# EPS_Battery_Controller_RLCL.net
KiCad netlist of a schematic drawn in Altium Designer
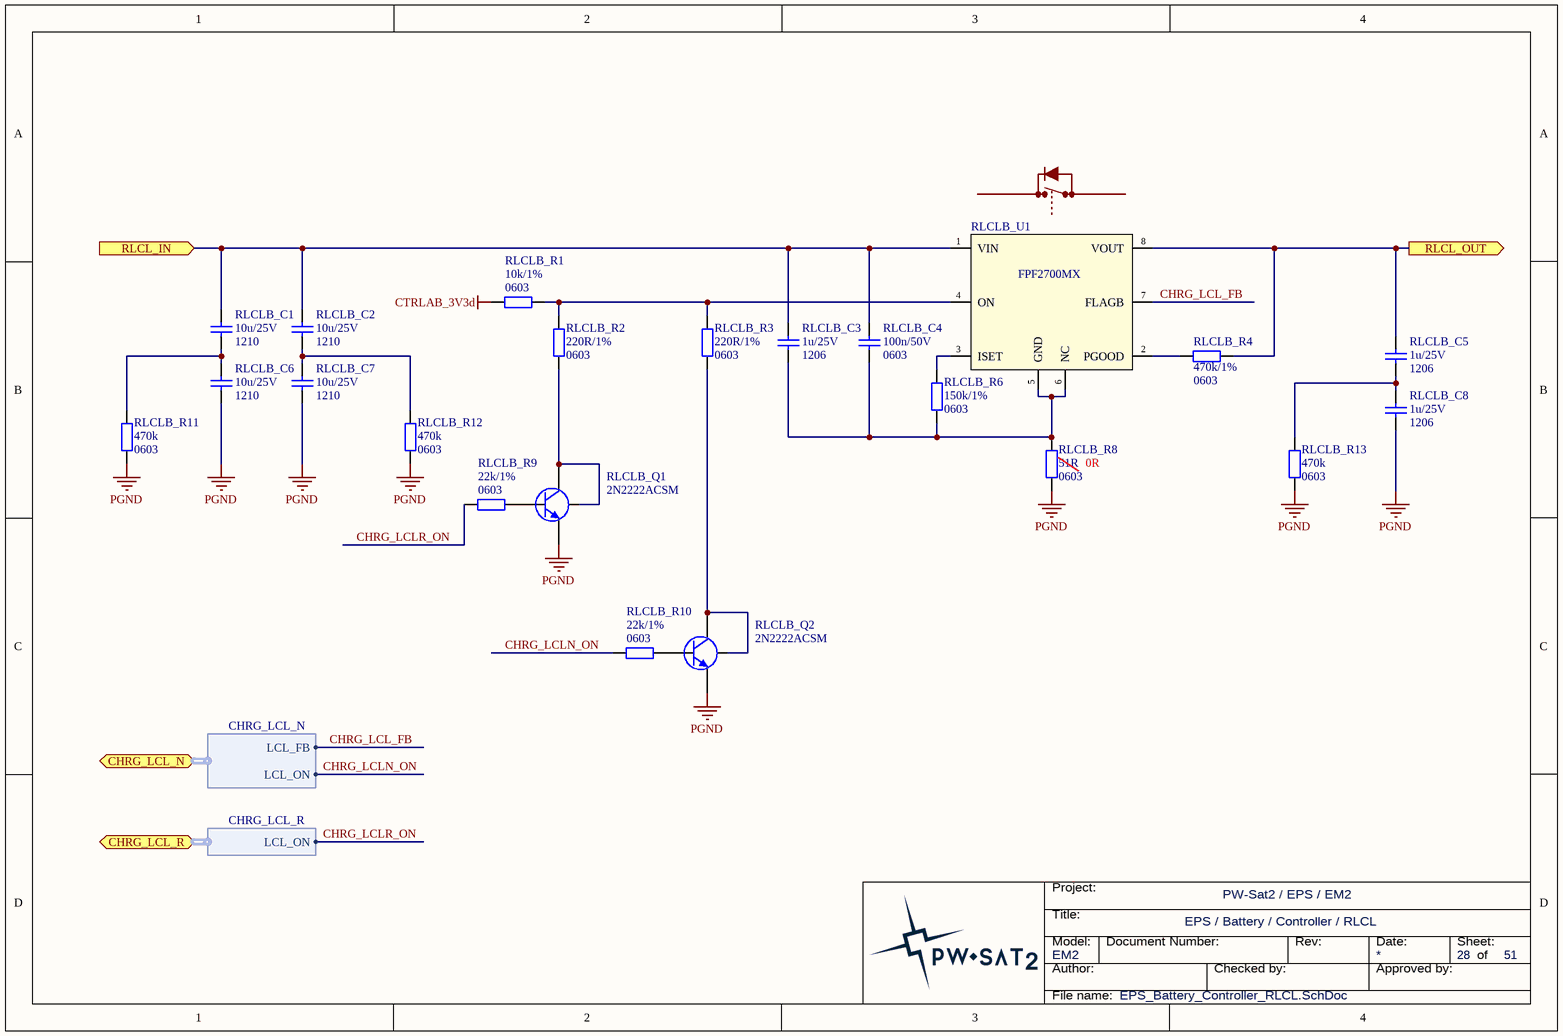
[diagram p0: EPS_Battery_Controller_RLCL.SchDoc]

(export (version "E")
  (design (tool "Eeschema 10.0.6"))
  (components
    (comp (ref "RLCLB_C1")
      (value "10u/25V")
      (footprint "SMD_Capacitor_1210")
      (description "Ceramic Cap Murata Automotive 10u/25V X7R 1210")
      (fields
        (field (name "MANUFACTURER") "Murata")
        (field (name "MANUFACTURERPARTNUMBER") "GCJ32ER71E106KA12L")
        (field (name "PACKAGE") "1210")
      )
      (libsource (lib "capacitors") (part "Cer_GCJ32ER71E106KA12L"))
    )
    (comp (ref "RLCLB_C2")
      (value "10u/25V")
      (footprint "SMD_Capacitor_1210")
      (description "Ceramic Cap Murata Automotive 10u/25V X7R 1210")
      (fields
        (field (name "MANUFACTURER") "Murata")
        (field (name "MANUFACTURERPARTNUMBER") "GCJ32ER71E106KA12L")
        (field (name "PACKAGE") "1210")
      )
      (libsource (lib "capacitors") (part "Cer_GCJ32ER71E106KA12L"))
    )
    (comp (ref "RLCLB_C3")
      (value "1u/25V")
      (footprint "SMD_Capacitor_1206")
      (description "Ceramic Cap Kemet COTS 1u/25V X7R 1206")
      (fields
        (field (name "MANUFACTURERPARTNUMBER") "C1206T105K3RALTU")
        (field (name "MANUFACTURER") "Kemet")
        (field (name "PACKAGE") "1206")
      )
      (libsource (lib "capacitors") (part "Cer_C1206T105K3RALTU"))
    )
    (comp (ref "RLCLB_C4")
      (value "100n/50V")
      (footprint "SMD_Capacitor_0603")
      (description "Ceramic Cap Murata Automotive 100n/50V X7R 0603")
      (fields
        (field (name "MANUFACTURER") "Murata")
        (field (name "MANUFACTURERPARTNUMBER") "GCJ188R71H104KA12D")
        (field (name "PACKAGE") "0603")
      )
      (libsource (lib "capacitors") (part "Cer_GCJ188R71H104KA12D"))
    )
    (comp (ref "RLCLB_C5")
      (value "1u/25V")
      (footprint "SMD_Capacitor_1206")
      (description "Ceramic Cap Kemet COTS 1u/25V X7R 1206")
      (fields
        (field (name "MANUFACTURERPARTNUMBER") "C1206T105K3RALTU")
        (field (name "MANUFACTURER") "Kemet")
        (field (name "PACKAGE") "1206")
      )
      (libsource (lib "capacitors") (part "Cer_C1206T105K3RALTU"))
    )
    (comp (ref "RLCLB_C6")
      (value "10u/25V")
      (footprint "SMD_Capacitor_1210")
      (description "Ceramic Cap Murata Automotive 10u/25V X7R 1210")
      (fields
        (field (name "MANUFACTURER") "Murata")
        (field (name "MANUFACTURERPARTNUMBER") "GCJ32ER71E106KA12L")
        (field (name "PACKAGE") "1210")
      )
      (libsource (lib "capacitors") (part "Cer_GCJ32ER71E106KA12L"))
    )
    (comp (ref "RLCLB_C7")
      (value "10u/25V")
      (footprint "SMD_Capacitor_1210")
      (description "Ceramic Cap Murata Automotive 10u/25V X7R 1210")
      (fields
        (field (name "MANUFACTURER") "Murata")
        (field (name "MANUFACTURERPARTNUMBER") "GCJ32ER71E106KA12L")
        (field (name "PACKAGE") "1210")
      )
      (libsource (lib "capacitors") (part "Cer_GCJ32ER71E106KA12L"))
    )
    (comp (ref "RLCLB_C8")
      (value "1u/25V")
      (footprint "SMD_Capacitor_1206")
      (description "Ceramic Cap Kemet COTS 1u/25V X7R 1206")
      (fields
        (field (name "MANUFACTURERPARTNUMBER") "C1206T105K3RALTU")
        (field (name "MANUFACTURER") "Kemet")
        (field (name "PACKAGE") "1206")
      )
      (libsource (lib "capacitors") (part "Cer_C1206T105K3RALTU"))
    )
    (comp (ref "RLCLB_Q1")
      (value "2N2222ACSM")
      (footprint "LCC1-4_BEC")
      (description "Silicon Planar Epitaxial NPN Transistor.")
      (fields (field (name "MANUFACTURER") "Semelab-TT"))
      (libsource (lib "transistors") (part "2N2222ACSM"))
    )
    (comp (ref "RLCLB_Q2")
      (value "2N2222ACSM")
      (footprint "LCC1-4_BEC")
      (description "Silicon Planar Epitaxial NPN Transistor.")
      (fields (field (name "MANUFACTURER") "Semelab-TT"))
      (libsource (lib "transistors") (part "2N2222ACSM"))
    )
    (comp (ref "RLCLB_R1")
      (value "10k/1%")
      (footprint "SMD_Resistor_0603")
      (fields (field (name "PACKAGE") "0603"))
      (libsource (lib "resistors") (part "Res"))
    )
    (comp (ref "RLCLB_R2")
      (value "220R/1%")
      (footprint "SMD_Resistor_0603")
      (fields (field (name "PACKAGE") "0603"))
      (libsource (lib "resistors") (part "Res"))
    )
    (comp (ref "RLCLB_R3")
      (value "220R/1%")
      (footprint "SMD_Resistor_0603")
      (fields (field (name "PACKAGE") "0603"))
      (libsource (lib "resistors") (part "Res"))
    )
    (comp (ref "RLCLB_R4")
      (value "470k/1%")
      (footprint "SMD_Resistor_0603")
      (fields (field (name "PACKAGE") "0603"))
      (libsource (lib "") (part "Res_2"))
    )
    (comp (ref "RLCLB_R6")
      (value "150k/1%")
      (footprint "SMD_Resistor_0603")
      (fields (field (name "PACKAGE") "0603"))
      (libsource (lib "resistors") (part "Res"))
    )
    (comp (ref "RLCLB_R8")
      (value "51R")
      (footprint "SMD_Resistor_0603")
      (fields (field (name "PACKAGE") "0603"))
      (libsource (lib "resistors") (part "Res"))
    )
    (comp (ref "RLCLB_R9")
      (value "22k/1%")
      (footprint "SMD_Resistor_0603")
      (fields (field (name "PACKAGE") "0603"))
      (libsource (lib "") (part "Res_1"))
    )
    (comp (ref "RLCLB_R10")
      (value "22k/1%")
      (footprint "SMD_Resistor_0603")
      (fields (field (name "PACKAGE") "0603"))
      (libsource (lib "") (part "Res_1"))
    )
    (comp (ref "RLCLB_R11")
      (value "470k")
      (footprint "SMD_Resistor_0603")
      (fields (field (name "PACKAGE") "0603"))
      (libsource (lib "resistors") (part "Res"))
    )
    (comp (ref "RLCLB_R12")
      (value "470k")
      (footprint "SMD_Resistor_0603")
      (fields (field (name "PACKAGE") "0603"))
      (libsource (lib "resistors") (part "Res"))
    )
    (comp (ref "RLCLB_R13")
      (value "470k")
      (footprint "SMD_Resistor_0603")
      (fields (field (name "PACKAGE") "0603"))
      (libsource (lib "resistors") (part "Res"))
    )
    (comp (ref "RLCLB_U1")
      (value "FPF2700MX")
      (footprint "SOIC-8-N")
      (description "Adj over-current protection 0.4-2A, Load Switch")
      (fields (field (name "MANUFACTURER") "Fairchild Semiconductor"))
      (libsource (lib "microcircuits") (part "FPF2700MX"))
    )
  )
  (nets
    (net (code "3") (name "/CHRG_LCLN_ON") (class "Default")
      (node (ref "RLCLB_R10") (pin "1") (pinfunction "1_1") (pintype "passive"))
    )
    (net (code "4") (name "/CHRG_LCLR_ON") (class "Default")
      (node (ref "RLCLB_R9") (pin "1") (pinfunction "1_1") (pintype "passive"))
    )
    (net (code "5") (name "/CHRG_LCL_FB") (class "Default")
      (node (ref "RLCLB_U1") (pin "7") (pinfunction "FLAGB_7") (pintype "passive"))
    )
    (net (code "6") (name "/RLCL_IN") (class "Default")
      (node (ref "RLCLB_C1") (pin "1") (pinfunction "1_1") (pintype "passive"))
      (node (ref "RLCLB_C2") (pin "1") (pinfunction "1_1") (pintype "passive"))
      (node (ref "RLCLB_C3") (pin "1") (pinfunction "1_1") (pintype "passive"))
      (node (ref "RLCLB_C4") (pin "1") (pinfunction "1_1") (pintype "passive"))
      (node (ref "RLCLB_U1") (pin "1") (pinfunction "VIN_1") (pintype "passive"))
    )
    (net (code "7") (name "/RLCL_OUT") (class "Default")
      (node (ref "RLCLB_C5") (pin "1") (pinfunction "1_1") (pintype "passive"))
      (node (ref "RLCLB_R4") (pin "2") (pinfunction "2_2") (pintype "passive"))
      (node (ref "RLCLB_U1") (pin "8") (pinfunction "VOUT_8") (pintype "passive"))
    )
    (net (code "10") (name "CTRLAB_3V3d") (class "Default")
      (node (ref "RLCLB_R1") (pin "2") (pinfunction "2_2") (pintype "passive"))
    )
    (net (code "11") (name "Net-(RLCLB_C1-Pad2)") (class "Default")
      (node (ref "RLCLB_C1") (pin "2") (pinfunction "2_2") (pintype "passive"))
      (node (ref "RLCLB_C6") (pin "1") (pinfunction "1_1") (pintype "passive"))
      (node (ref "RLCLB_R11") (pin "1") (pinfunction "1_1") (pintype "passive"))
    )
    (net (code "12") (name "Net-(RLCLB_C2-Pad2)") (class "Default")
      (node (ref "RLCLB_C2") (pin "2") (pinfunction "2_2") (pintype "passive"))
      (node (ref "RLCLB_C7") (pin "1") (pinfunction "1_1") (pintype "passive"))
      (node (ref "RLCLB_R12") (pin "1") (pinfunction "1_1") (pintype "passive"))
    )
    (net (code "13") (name "Net-(RLCLB_C5-Pad2)") (class "Default")
      (node (ref "RLCLB_C5") (pin "2") (pinfunction "2_2") (pintype "passive"))
      (node (ref "RLCLB_C8") (pin "1") (pinfunction "1_1") (pintype "passive"))
      (node (ref "RLCLB_R13") (pin "1") (pinfunction "1_1") (pintype "passive"))
    )
    (net (code "14") (name "Net-(RLCLB_Q1-PadB)") (class "Default")
      (node (ref "RLCLB_Q1") (pin "B") (pinfunction "B_B") (pintype "passive"))
      (node (ref "RLCLB_R9") (pin "2") (pinfunction "2_2") (pintype "passive"))
    )
    (net (code "15") (name "Net-(RLCLB_Q1-PadC)") (class "Default")
      (node (ref "RLCLB_Q1") (pin "C") (pinfunction "C_C") (pintype "passive"))
      (node (ref "RLCLB_Q1") (pin "Shield") (pinfunction "Shield_Shield") (pintype "passive"))
      (node (ref "RLCLB_R2") (pin "2") (pinfunction "2_2") (pintype "passive"))
    )
    (net (code "16") (name "Net-(RLCLB_Q2-PadB)") (class "Default")
      (node (ref "RLCLB_Q2") (pin "B") (pinfunction "B_B") (pintype "passive"))
      (node (ref "RLCLB_R10") (pin "2") (pinfunction "2_2") (pintype "passive"))
    )
    (net (code "17") (name "Net-(RLCLB_Q2-PadC)") (class "Default")
      (node (ref "RLCLB_Q2") (pin "C") (pinfunction "C_C") (pintype "passive"))
      (node (ref "RLCLB_Q2") (pin "Shield") (pinfunction "Shield_Shield") (pintype "passive"))
      (node (ref "RLCLB_R3") (pin "2") (pinfunction "2_2") (pintype "passive"))
    )
    (net (code "18") (name "Net-(RLCLB_U1-GND)") (class "Default")
      (node (ref "RLCLB_C3") (pin "2") (pinfunction "2_2") (pintype "passive"))
      (node (ref "RLCLB_C4") (pin "2") (pinfunction "2_2") (pintype "passive"))
      (node (ref "RLCLB_R6") (pin "2") (pinfunction "2_2") (pintype "passive"))
      (node (ref "RLCLB_R8") (pin "1") (pinfunction "1_1") (pintype "passive"))
      (node (ref "RLCLB_U1") (pin "5") (pinfunction "GND_5") (pintype "passive"))
      (node (ref "RLCLB_U1") (pin "6") (pinfunction "NC_6") (pintype "passive"))
    )
    (net (code "19") (name "Net-(RLCLB_U1-ISET)") (class "Default")
      (node (ref "RLCLB_R6") (pin "1") (pinfunction "1_1") (pintype "passive"))
      (node (ref "RLCLB_U1") (pin "3") (pinfunction "ISET_3") (pintype "passive"))
    )
    (net (code "20") (name "Net-(RLCLB_U1-ON)") (class "Default")
      (node (ref "RLCLB_R1") (pin "1") (pinfunction "1_1") (pintype "passive"))
      (node (ref "RLCLB_R2") (pin "1") (pinfunction "1_1") (pintype "passive"))
      (node (ref "RLCLB_R3") (pin "1") (pinfunction "1_1") (pintype "passive"))
      (node (ref "RLCLB_U1") (pin "4") (pinfunction "ON_4") (pintype "passive"))
    )
    (net (code "21") (name "Net-(RLCLB_U1-PGOOD)") (class "Default")
      (node (ref "RLCLB_R4") (pin "1") (pinfunction "1_1") (pintype "passive"))
      (node (ref "RLCLB_U1") (pin "2") (pinfunction "PGOOD_2") (pintype "passive"))
    )
    (net (code "22") (name "PGND") (class "Default")
      (node (ref "RLCLB_C6") (pin "2") (pinfunction "2_2") (pintype "passive"))
      (node (ref "RLCLB_C7") (pin "2") (pinfunction "2_2") (pintype "passive"))
      (node (ref "RLCLB_C8") (pin "2") (pinfunction "2_2") (pintype "passive"))
      (node (ref "RLCLB_Q1") (pin "E") (pinfunction "E_E") (pintype "passive"))
      (node (ref "RLCLB_Q2") (pin "E") (pinfunction "E_E") (pintype "passive"))
      (node (ref "RLCLB_R11") (pin "2") (pinfunction "2_2") (pintype "passive"))
      (node (ref "RLCLB_R12") (pin "2") (pinfunction "2_2") (pintype "passive"))
      (node (ref "RLCLB_R13") (pin "2") (pinfunction "2_2") (pintype "passive"))
      (node (ref "RLCLB_R8") (pin "2") (pinfunction "2_2") (pintype "passive"))
    )
  )
)
